# SW6106_A_A_C_MCU_LED.net
KiCad netlist of a schematic drawn in Altium Designer
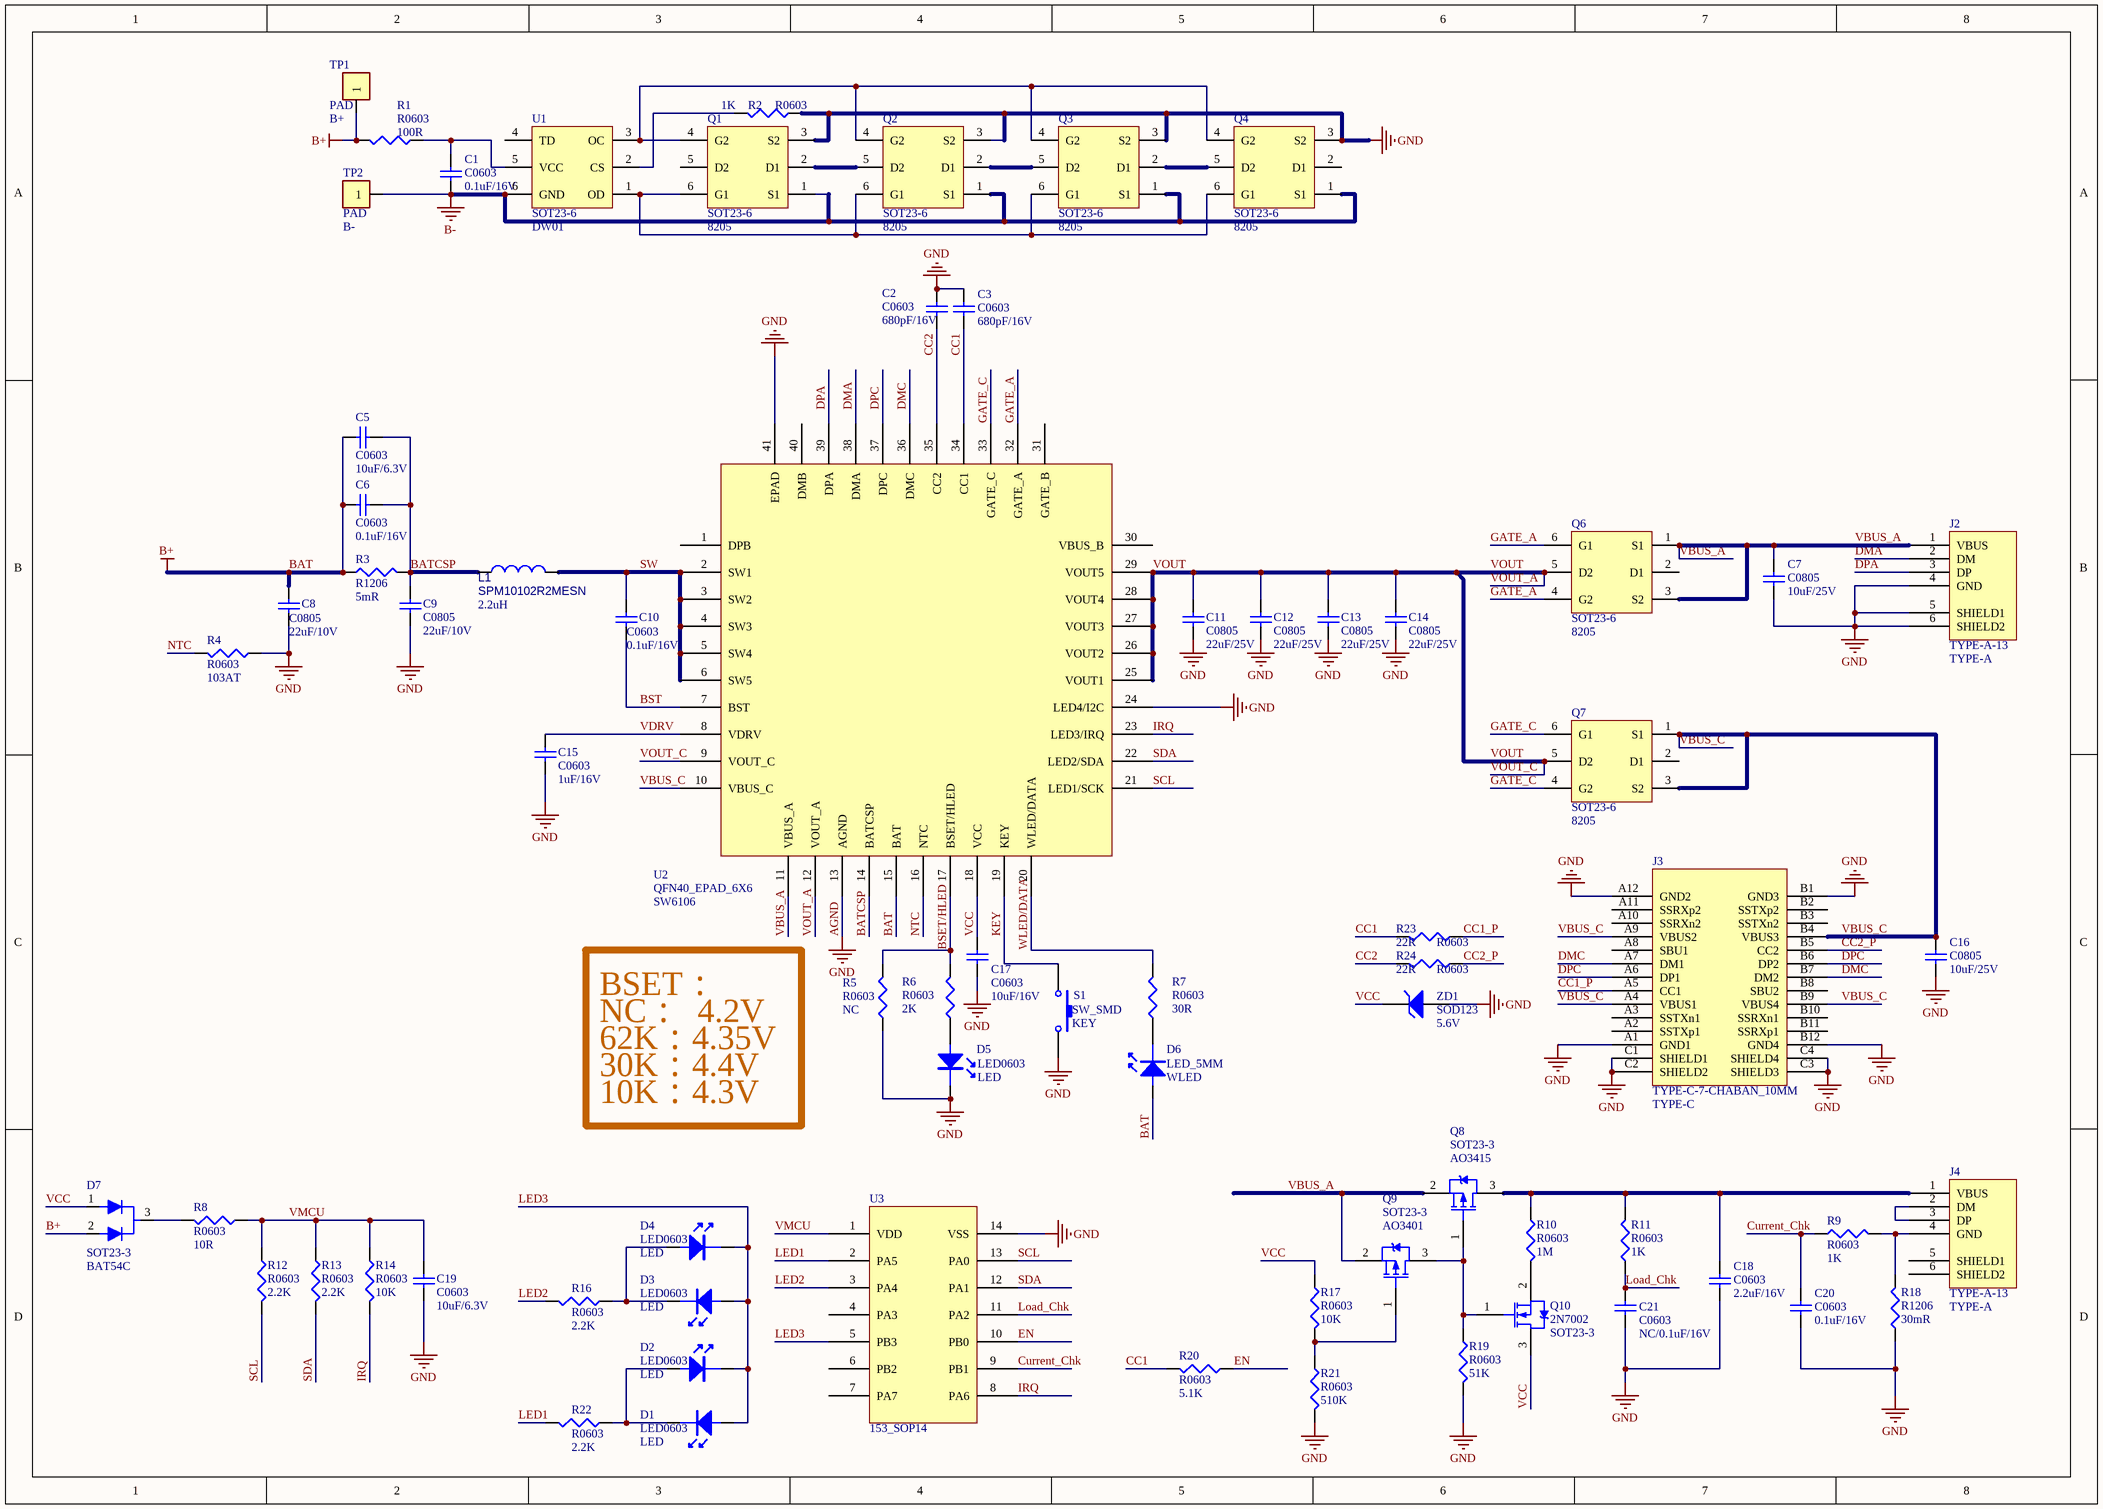
[diagram p0: SW6106+A+A+C+MCU+LED.SchDoc]

(export (version "E")
  (design (tool "Eeschema 10.0.6"))
  (components
    (comp (ref "C1")
      (value "C0603")
      (footprint "C0603")
      (description "Capacitor")
      (fields (field (name "ALTIUM_VALUE") "0.1uF/16V") (field (name "PUBLISHER") "Altium Limited"))
      (libsource (lib "*") (part "Cap"))
    )
    (comp (ref "C2")
      (value "C0603")
      (footprint "C0603")
      (description "Capacitor")
      (fields (field (name "ALTIUM_VALUE") "680pF/16V") (field (name "PUBLISHER") "Altium Limited"))
      (libsource (lib "*") (part "CAP0603"))
    )
    (comp (ref "C3")
      (value "C0603")
      (footprint "C0603")
      (description "Capacitor")
      (fields (field (name "ALTIUM_VALUE") "680pF/16V") (field (name "PUBLISHER") "Altium Limited"))
      (libsource (lib "*") (part "CAP0603"))
    )
    (comp (ref "C5")
      (value "C0603")
      (footprint "C0603")
      (description "Capacitor")
      (fields (field (name "ALTIUM_VALUE") "10uF/6.3V") (field (name "PUBLISHER") "Altium Limited"))
      (libsource (lib "*") (part "CAP0603"))
    )
    (comp (ref "C6")
      (value "C0603")
      (footprint "C0603")
      (description "Capacitor")
      (fields (field (name "ALTIUM_VALUE") "0.1uF/16V") (field (name "PUBLISHER") "Altium Limited"))
      (libsource (lib "*") (part "CAP0603"))
    )
    (comp (ref "C7")
      (value "C0805")
      (footprint "C0805")
      (description "Capacitor")
      (fields (field (name "ALTIUM_VALUE") "10uF/25V") (field (name "PUBLISHER") "Altium Limited"))
      (libsource (lib "*") (part "CAP0603"))
    )
    (comp (ref "C8")
      (value "C0805")
      (footprint "C0805")
      (description "Capacitor")
      (fields (field (name "ALTIUM_VALUE") "22uF/10V") (field (name "PUBLISHER") "Altium Limited"))
      (libsource (lib "*") (part "CAP0805"))
    )
    (comp (ref "C9")
      (value "C0805")
      (footprint "C0805")
      (description "Capacitor")
      (fields (field (name "ALTIUM_VALUE") "22uF/10V") (field (name "PUBLISHER") "Altium Limited"))
      (libsource (lib "*") (part "CAP0805"))
    )
    (comp (ref "C10")
      (value "C0603")
      (footprint "C0603")
      (description "Capacitor")
      (fields (field (name "ALTIUM_VALUE") "0.1uF/16V") (field (name "PUBLISHER") "Altium Limited"))
      (libsource (lib "*") (part "CAP0603"))
    )
    (comp (ref "C11")
      (value "C0805")
      (footprint "C0805")
      (description "Capacitor")
      (fields (field (name "ALTIUM_VALUE") "22uF/25V") (field (name "PUBLISHER") "Altium Limited"))
      (libsource (lib "*") (part "CAP0805"))
    )
    (comp (ref "C12")
      (value "C0805")
      (footprint "C0805")
      (description "Capacitor")
      (fields (field (name "ALTIUM_VALUE") "22uF/25V") (field (name "PUBLISHER") "Altium Limited"))
      (libsource (lib "*") (part "CAP0805"))
    )
    (comp (ref "C13")
      (value "C0805")
      (footprint "C0805")
      (description "Capacitor")
      (fields (field (name "ALTIUM_VALUE") "22uF/25V") (field (name "PUBLISHER") "Altium Limited"))
      (libsource (lib "*") (part "CAP0805"))
    )
    (comp (ref "C14")
      (value "C0805")
      (footprint "C0805")
      (description "Capacitor")
      (fields (field (name "ALTIUM_VALUE") "22uF/25V") (field (name "PUBLISHER") "Altium Limited"))
      (libsource (lib "*") (part "CAP0805"))
    )
    (comp (ref "C15")
      (value "C0603")
      (footprint "C0603")
      (description "Capacitor")
      (fields (field (name "ALTIUM_VALUE") "1uF/16V") (field (name "PUBLISHER") "Altium Limited"))
      (libsource (lib "*") (part "CAP0603"))
    )
    (comp (ref "C16")
      (value "C0805")
      (footprint "C0805")
      (description "Capacitor")
      (fields (field (name "ALTIUM_VALUE") "10uF/25V") (field (name "PUBLISHER") "Altium Limited"))
      (libsource (lib "*") (part "CAP0603"))
    )
    (comp (ref "C17")
      (value "C0603")
      (footprint "C0603")
      (description "Capacitor")
      (fields (field (name "ALTIUM_VALUE") "10uF/16V") (field (name "PUBLISHER") "Altium Limited"))
      (libsource (lib "*") (part "CAP0603"))
    )
    (comp (ref "C18")
      (value "C0603")
      (footprint "C0603")
      (description "Capacitor")
      (fields (field (name "ALTIUM_VALUE") "2.2uF/16V") (field (name "PUBLISHER") "Altium Limited"))
      (libsource (lib "*") (part "CAP0603"))
    )
    (comp (ref "C19")
      (value "C0603")
      (footprint "C0603")
      (description "Capacitor")
      (fields (field (name "ALTIUM_VALUE") "10uF/6.3V") (field (name "PUBLISHER") "Altium Limited"))
      (libsource (lib "*") (part "CAP0603"))
    )
    (comp (ref "C20")
      (value "C0603")
      (footprint "C0603")
      (description "Capacitor")
      (fields (field (name "ALTIUM_VALUE") "0.1uF/16V") (field (name "PUBLISHER") "Altium Limited"))
      (libsource (lib "*") (part "CAP0603"))
    )
    (comp (ref "C21")
      (value "C0603")
      (footprint "C0603")
      (description "Capacitor")
      (fields (field (name "ALTIUM_VALUE") "NC/0.1uF/16V") (field (name "PUBLISHER") "Altium Limited"))
      (libsource (lib "*") (part "CAP0603"))
    )
    (comp (ref "D1") (value "LED") (footprint "LED0603") (libsource (lib "*") (part "LED")))
    (comp (ref "D2") (value "LED") (footprint "LED0603") (libsource (lib "*") (part "LED")))
    (comp (ref "D3") (value "LED") (footprint "LED0603") (libsource (lib "*") (part "LED")))
    (comp (ref "D4") (value "LED") (footprint "LED0603") (libsource (lib "*") (part "LED")))
    (comp (ref "D5") (value "LED") (footprint "LED0603") (libsource (lib "*") (part "LED")))
    (comp (ref "D6")
      (value "WLED")
      (footprint "LED_5MM")
      (fields (field (name "FOOTPRINF") "LED_5MM") (field (name "Comment") "LED_5MM"))
      (libsource (lib "*") (part "LED"))
    )
    (comp (ref "D7") (value "BAT54C") (footprint "SOT23-3") (libsource (lib "Schlib1-2012") (part "D3")))
    (comp (ref "J2")
      (value "TYPE-A")
      (footprint "TYPE-A-13")
      (fields (field (name "FOOTPRINF") "TYPE-A-13") (field (name "Comment") "TYPE-A-1"))
      (libsource (lib "*") (part "TYPE-A-1"))
    )
    (comp (ref "J3")
      (value "TYPE-C")
      (footprint "TYPE-C-7-CHABAN_10MM")
      (libsource (lib "*") (part "TYPE-C"))
    )
    (comp (ref "J4")
      (value "TYPE-A")
      (footprint "PIE10-USB")
      (fields (field (name "FOOTPRINF") "TYPE-A-13") (field (name "Comment") "TYPE-A-1"))
      (libsource (lib "*") (part "TYPE-A-1"))
    )
    (comp (ref "L1")
      (value "SPM10102R2MESN")
      (footprint "INDUCTOR_SPM1010")
      (fields (field (name "ALTIUM_VALUE") "2.2uH"))
      (libsource (lib "*") (part "INDUCTOR"))
    )
    (comp (ref "Q1")
      (value "8205")
      (footprint "SOT23-6")
      (fields (field (name "FOOTPRINF") "SOT23-6"))
      (libsource (lib "*") (part "8205B"))
    )
    (comp (ref "Q2")
      (value "8205")
      (footprint "SOT23-6")
      (fields (field (name "FOOTPRINF") "SOT23-6"))
      (libsource (lib "*") (part "8205B"))
    )
    (comp (ref "Q3")
      (value "8205")
      (footprint "SOT23-6")
      (fields (field (name "FOOTPRINF") "SOT23-6"))
      (libsource (lib "*") (part "8205B"))
    )
    (comp (ref "Q4")
      (value "8205")
      (footprint "SOT23-6")
      (fields (field (name "FOOTPRINF") "SOT23-6"))
      (libsource (lib "*") (part "8205B"))
    )
    (comp (ref "Q6")
      (value "8205")
      (footprint "SOT23-6")
      (fields (field (name "FOOTPRINF") "SOT23-6"))
      (libsource (lib "") (part "8205B_1"))
    )
    (comp (ref "Q7")
      (value "8205")
      (footprint "SOT23-6")
      (fields (field (name "FOOTPRINF") "SOT23-6"))
      (libsource (lib "") (part "8205B_1"))
    )
    (comp (ref "Q8")
      (value "AO3415")
      (footprint "SOT23-3")
      (description "P-Channel Power MOSFET")
      (fields (field (name "Comment") "PMOS-2") (field (name "PUBLISHER") "Altium Limited"))
      (libsource (lib "Miscellaneous Devices") (part "PMOS-2"))
    )
    (comp (ref "Q9")
      (value "AO3401")
      (footprint "SOT23-3")
      (description "P-Channel Power MOSFET")
      (fields (field (name "Comment") "PMOS-2") (field (name "PUBLISHER") "Altium Limited"))
      (libsource (lib "Miscellaneous Devices") (part "PMOS-2"))
    )
    (comp (ref "Q10")
      (value "2N7002")
      (footprint "SOT23-3")
      (description "N-Channel Power MOSFET")
      (fields (field (name "Comment") "NMOS-2") (field (name "PUBLISHER") "Altium Limited"))
      (libsource (lib "Miscellaneous Devices") (part "NMOS-2"))
    )
    (comp (ref "R1")
      (value "R0603")
      (footprint "R0603")
      (description "Resistor")
      (fields (field (name "ALTIUM_VALUE") "100R") (field (name "PUBLISHER") "Altium Limited"))
      (libsource (lib "*") (part "Res3"))
    )
    (comp (ref "R2")
      (value "R0603")
      (footprint "R0603")
      (description "Resistor")
      (fields (field (name "ALTIUM_VALUE") "1K") (field (name "PUBLISHER") "Altium Limited"))
      (libsource (lib "*") (part "Res3"))
    )
    (comp (ref "R3")
      (value "R1206")
      (footprint "R1206")
      (description "Resistor")
      (fields (field (name "ALTIUM_VALUE") "5mR") (field (name "PUBLISHER") "Altium Limited"))
      (libsource (lib "*") (part "RES"))
    )
    (comp (ref "R4")
      (value "R0603")
      (footprint "R0603")
      (description "Resistor")
      (fields (field (name "ALTIUM_VALUE") "103AT") (field (name "PUBLISHER") "Altium Limited"))
      (libsource (lib "*") (part "RES"))
    )
    (comp (ref "R5")
      (value "R0603")
      (footprint "R0603")
      (description "Resistor")
      (fields (field (name "ALTIUM_VALUE") "NC") (field (name "PUBLISHER") "Altium Limited"))
      (libsource (lib "*") (part "RES"))
    )
    (comp (ref "R6")
      (value "R0603")
      (footprint "R0603")
      (description "Resistor")
      (fields (field (name "ALTIUM_VALUE") "2K") (field (name "PUBLISHER") "Altium Limited"))
      (libsource (lib "*") (part "RES"))
    )
    (comp (ref "R7")
      (value "R0603")
      (footprint "R0603")
      (description "Resistor")
      (fields (field (name "ALTIUM_VALUE") "30R") (field (name "PUBLISHER") "Altium Limited"))
      (libsource (lib "*") (part "RES"))
    )
    (comp (ref "R8")
      (value "R0603")
      (footprint "R0603")
      (description "Resistor")
      (fields (field (name "ALTIUM_VALUE") "10R") (field (name "PUBLISHER") "Altium Limited"))
      (libsource (lib "*") (part "RES"))
    )
    (comp (ref "R9")
      (value "R0603")
      (footprint "R0603")
      (description "Resistor")
      (fields (field (name "ALTIUM_VALUE") "1K") (field (name "PUBLISHER") "Altium Limited"))
      (libsource (lib "*") (part "RES"))
    )
    (comp (ref "R10")
      (value "R0603")
      (footprint "R0603")
      (description "Resistor")
      (fields (field (name "ALTIUM_VALUE") "1M") (field (name "PUBLISHER") "Altium Limited"))
      (libsource (lib "*") (part "RES"))
    )
    (comp (ref "R11")
      (value "R0603")
      (footprint "R0603")
      (description "Resistor")
      (fields (field (name "ALTIUM_VALUE") "1K") (field (name "PUBLISHER") "Altium Limited"))
      (libsource (lib "*") (part "RES"))
    )
    (comp (ref "R12")
      (value "R0603")
      (footprint "R0603")
      (description "Resistor")
      (fields (field (name "ALTIUM_VALUE") "2.2K") (field (name "PUBLISHER") "Altium Limited"))
      (libsource (lib "*") (part "RES"))
    )
    (comp (ref "R13")
      (value "R0603")
      (footprint "R0603")
      (description "Resistor")
      (fields (field (name "ALTIUM_VALUE") "2.2K") (field (name "PUBLISHER") "Altium Limited"))
      (libsource (lib "*") (part "RES"))
    )
    (comp (ref "R14")
      (value "R0603")
      (footprint "R0603")
      (description "Resistor")
      (fields (field (name "ALTIUM_VALUE") "10K") (field (name "PUBLISHER") "Altium Limited"))
      (libsource (lib "*") (part "RES"))
    )
    (comp (ref "R16")
      (value "R0603")
      (footprint "R0603")
      (description "Resistor")
      (fields (field (name "ALTIUM_VALUE") "2.2K") (field (name "PUBLISHER") "Altium Limited"))
      (libsource (lib "*") (part "RES"))
    )
    (comp (ref "R17")
      (value "R0603")
      (footprint "R0603")
      (description "Resistor")
      (fields (field (name "ALTIUM_VALUE") "10K") (field (name "PUBLISHER") "Altium Limited"))
      (libsource (lib "*") (part "RES"))
    )
    (comp (ref "R18")
      (value "R1206")
      (footprint "C-1206A")
      (description "Resistor")
      (fields (field (name "ALTIUM_VALUE") "30mR") (field (name "PUBLISHER") "Altium Limited"))
      (libsource (lib "*") (part "RES"))
    )
    (comp (ref "R19")
      (value "R0603")
      (footprint "R0603")
      (description "Resistor")
      (fields (field (name "ALTIUM_VALUE") "51K") (field (name "PUBLISHER") "Altium Limited"))
      (libsource (lib "*") (part "RES"))
    )
    (comp (ref "R20")
      (value "R0603")
      (footprint "R0603")
      (description "Resistor")
      (fields (field (name "ALTIUM_VALUE") "5.1K") (field (name "PUBLISHER") "Altium Limited"))
      (libsource (lib "*") (part "RES"))
    )
    (comp (ref "R21")
      (value "R0603")
      (footprint "R0603")
      (description "Resistor")
      (fields (field (name "ALTIUM_VALUE") "510K") (field (name "PUBLISHER") "Altium Limited"))
      (libsource (lib "*") (part "RES"))
    )
    (comp (ref "R22")
      (value "R0603")
      (footprint "R0603")
      (description "Resistor")
      (fields (field (name "ALTIUM_VALUE") "2.2K") (field (name "PUBLISHER") "Altium Limited"))
      (libsource (lib "*") (part "RES"))
    )
    (comp (ref "R23")
      (value "R0603")
      (footprint "R0603")
      (description "Resistor")
      (fields (field (name "ALTIUM_VALUE") "22R") (field (name "PUBLISHER") "Altium Limited"))
      (libsource (lib "*") (part "RES"))
    )
    (comp (ref "R24")
      (value "R0603")
      (footprint "R0603")
      (description "Resistor")
      (fields (field (name "ALTIUM_VALUE") "22R") (field (name "PUBLISHER") "Altium Limited"))
      (libsource (lib "*") (part "RES"))
    )
    (comp (ref "S1")
      (value "KEY")
      (footprint "SW_SMD")
      (fields (field (name "FOOTPRINF") "SW_SMD"))
      (libsource (lib "*") (part "SW K"))
    )
    (comp (ref "TP1") (value "B+") (footprint "PAD") (libsource (lib "*") (part "Test Point")))
    (comp (ref "TP2") (value "B-") (footprint "PAD") (libsource (lib "") (part "Test Point_1")))
    (comp (ref "U1")
      (value "DW01")
      (footprint "SOT23-6")
      (fields (field (name "FOOTPRINF") "SOT23-6"))
      (libsource (lib "*") (part "DW01"))
    )
    (comp (ref "U2")
      (value "SW6106")
      (footprint "QFN40_EPAD_6X6")
      (libsource (lib "TEST") (part "SW6106_AFC"))
    )
    (comp (ref "U3") (value "153_SOP14") (libsource (lib "TEST") (part "153_SOP14")))
    (comp (ref "ZD1")
      (value "SOD123")
      (footprint "SOD-123")
      (description "Zener Diode")
      (fields (field (name "ALTIUM_UNNAMED_1") "5.6V"))
      (libsource (lib "Miscellaneous Devices") (part "D Zener"))
    )
  )
  (nets
    (net (code "1") (name "/BATCSP") (class "Default")
      (node (ref "C5") (pin "2") (pinfunction "2_2") (pintype "passive"))
      (node (ref "C6") (pin "2") (pinfunction "2_2") (pintype "passive"))
      (node (ref "C9") (pin "2") (pinfunction "2_2") (pintype "passive"))
      (node (ref "L1") (pin "1") (pinfunction "1_1") (pintype "passive"))
      (node (ref "R3") (pin "2") (pinfunction "2_2") (pintype "passive"))
      (node (ref "U2") (pin "14") (pinfunction "BATCSP_14") (pintype "passive"))
    )
    (net (code "2") (name "/BSET{slash}HLED") (class "Default")
      (node (ref "R5") (pin "2") (pinfunction "2_2") (pintype "passive"))
      (node (ref "R6") (pin "2") (pinfunction "2_2") (pintype "passive"))
      (node (ref "U2") (pin "17") (pinfunction "BSET/HLED_17") (pintype "passive"))
    )
    (net (code "3") (name "/BST") (class "Default")
      (node (ref "C10") (pin "1") (pinfunction "1_1") (pintype "passive"))
      (node (ref "U2") (pin "7") (pinfunction "BST_7") (pintype "passive"))
    )
    (net (code "4") (name "/CC1") (class "Default")
      (node (ref "C3") (pin "1") (pinfunction "1_1") (pintype "passive"))
      (node (ref "R20") (pin "2") (pinfunction "2_2") (pintype "passive"))
      (node (ref "R23") (pin "2") (pinfunction "2_2") (pintype "passive"))
      (node (ref "U2") (pin "34") (pinfunction "CC1_34") (pintype "passive"))
    )
    (net (code "5") (name "/CC1_P") (class "Default")
      (node (ref "J3") (pin "A5") (pinfunction "CC1_A5") (pintype "passive"))
      (node (ref "R23") (pin "1") (pinfunction "1_1") (pintype "passive"))
    )
    (net (code "6") (name "/CC2") (class "Default")
      (node (ref "C2") (pin "1") (pinfunction "1_1") (pintype "passive"))
      (node (ref "R24") (pin "2") (pinfunction "2_2") (pintype "passive"))
      (node (ref "U2") (pin "35") (pinfunction "CC2_35") (pintype "passive"))
    )
    (net (code "7") (name "/CC2_P") (class "Default")
      (node (ref "J3") (pin "B5") (pinfunction "CC2_B5") (pintype "passive"))
      (node (ref "R24") (pin "1") (pinfunction "1_1") (pintype "passive"))
    )
    (net (code "8") (name "/Current_Chk") (class "Default")
      (node (ref "C20") (pin "2") (pinfunction "2_2") (pintype "passive"))
      (node (ref "R9") (pin "1") (pinfunction "1_1") (pintype "passive"))
      (node (ref "U3") (pin "9") (pinfunction "PB1_9") (pintype "passive"))
    )
    (net (code "9") (name "/DMA") (class "Default")
      (node (ref "J2") (pin "2") (pinfunction "DM_2") (pintype "passive"))
      (node (ref "U2") (pin "38") (pinfunction "DMA_38") (pintype "passive"))
    )
    (net (code "10") (name "/DMC") (class "Default")
      (node (ref "J3") (pin "A7") (pinfunction "DM1_A7") (pintype "passive"))
      (node (ref "J3") (pin "B7") (pinfunction "DM2_B7") (pintype "passive"))
      (node (ref "U2") (pin "36") (pinfunction "DMC_36") (pintype "passive"))
    )
    (net (code "11") (name "/DPA") (class "Default")
      (node (ref "J2") (pin "3") (pinfunction "DP_3") (pintype "passive"))
      (node (ref "U2") (pin "39") (pinfunction "DPA_39") (pintype "passive"))
    )
    (net (code "12") (name "/DPC") (class "Default")
      (node (ref "J3") (pin "A6") (pinfunction "DP1_A6") (pintype "passive"))
      (node (ref "J3") (pin "B6") (pinfunction "DP2_B6") (pintype "passive"))
      (node (ref "U2") (pin "37") (pinfunction "DPC_37") (pintype "passive"))
    )
    (net (code "13") (name "/EN") (class "Default")
      (node (ref "R20") (pin "1") (pinfunction "1_1") (pintype "passive"))
      (node (ref "U3") (pin "10") (pinfunction "PB0_10") (pintype "passive"))
    )
    (net (code "14") (name "/GATE_A") (class "Default")
      (node (ref "Q6") (pin "4") (pinfunction "G2_4") (pintype "passive"))
      (node (ref "Q6") (pin "6") (pinfunction "G1_6") (pintype "passive"))
      (node (ref "U2") (pin "32") (pinfunction "GATE_A_32") (pintype "passive"))
    )
    (net (code "15") (name "/GATE_C") (class "Default")
      (node (ref "Q7") (pin "4") (pinfunction "G2_4") (pintype "passive"))
      (node (ref "Q7") (pin "6") (pinfunction "G1_6") (pintype "passive"))
      (node (ref "U2") (pin "33") (pinfunction "GATE_C_33") (pintype "passive"))
    )
    (net (code "16") (name "/IRQ") (class "Default")
      (node (ref "R14") (pin "2") (pinfunction "2_2") (pintype "passive"))
      (node (ref "U2") (pin "23") (pinfunction "LED3/IRQ_23") (pintype "passive"))
      (node (ref "U3") (pin "8") (pinfunction "PA6_8") (pintype "passive"))
    )
    (net (code "17") (name "/KEY") (class "Default")
      (node (ref "S1") (pin "1") (pinfunction "1_1") (pintype "passive"))
      (node (ref "U2") (pin "19") (pinfunction "KEY_19") (pintype "passive"))
    )
    (net (code "18") (name "/LED1") (class "Default")
      (node (ref "R22") (pin "2") (pinfunction "2_2") (pintype "passive"))
      (node (ref "U3") (pin "2") (pinfunction "PA5_2") (pintype "passive"))
    )
    (net (code "19") (name "/LED2") (class "Default")
      (node (ref "R16") (pin "2") (pinfunction "2_2") (pintype "passive"))
      (node (ref "U3") (pin "3") (pinfunction "PA4_3") (pintype "passive"))
    )
    (net (code "20") (name "/LED3") (class "Default")
      (node (ref "D1") (pin "1") (pinfunction "A_1") (pintype "passive"))
      (node (ref "D2") (pin "2") (pinfunction "K_2") (pintype "passive"))
      (node (ref "D3") (pin "1") (pinfunction "A_1") (pintype "passive"))
      (node (ref "D4") (pin "2") (pinfunction "K_2") (pintype "passive"))
      (node (ref "U3") (pin "5") (pinfunction "PB3_5") (pintype "passive"))
    )
    (net (code "21") (name "/Load_Chk") (class "Default")
      (node (ref "C21") (pin "2") (pinfunction "2_2") (pintype "passive"))
      (node (ref "R11") (pin "1") (pinfunction "1_1") (pintype "passive"))
      (node (ref "U3") (pin "11") (pinfunction "PA2_11") (pintype "passive"))
    )
    (net (code "22") (name "/NTC") (class "Default")
      (node (ref "R4") (pin "2") (pinfunction "2_2") (pintype "passive"))
      (node (ref "U2") (pin "16") (pinfunction "NTC_16") (pintype "passive"))
    )
    (net (code "23") (name "/SCL") (class "Default")
      (node (ref "R12") (pin "2") (pinfunction "2_2") (pintype "passive"))
      (node (ref "U2") (pin "21") (pinfunction "LED1/SCK_21") (pintype "passive"))
      (node (ref "U3") (pin "13") (pinfunction "PA0_13") (pintype "passive"))
    )
    (net (code "24") (name "/SDA") (class "Default")
      (node (ref "R13") (pin "2") (pinfunction "2_2") (pintype "passive"))
      (node (ref "U2") (pin "22") (pinfunction "LED2/SDA_22") (pintype "passive"))
      (node (ref "U3") (pin "12") (pinfunction "PA1_12") (pintype "passive"))
    )
    (net (code "25") (name "/SW") (class "Default")
      (node (ref "C10") (pin "2") (pinfunction "2_2") (pintype "passive"))
      (node (ref "L1") (pin "2") (pinfunction "2_2") (pintype "passive"))
      (node (ref "U2") (pin "2") (pinfunction "SW1_2") (pintype "passive"))
      (node (ref "U2") (pin "3") (pinfunction "SW2_3") (pintype "passive"))
      (node (ref "U2") (pin "4") (pinfunction "SW3_4") (pintype "passive"))
      (node (ref "U2") (pin "5") (pinfunction "SW4_5") (pintype "passive"))
      (node (ref "U2") (pin "6") (pinfunction "SW5_6") (pintype "passive"))
    )
    (net (code "26") (name "/VBUS_A") (class "Default")
      (node (ref "C7") (pin "2") (pinfunction "2_2") (pintype "passive"))
      (node (ref "J2") (pin "1") (pinfunction "VBUS_1") (pintype "passive"))
      (node (ref "Q6") (pin "1") (pinfunction "S1_1") (pintype "passive"))
      (node (ref "Q6") (pin "3") (pinfunction "S2_3") (pintype "passive"))
      (node (ref "Q8") (pin "2") (pinfunction "S_2") (pintype "passive"))
      (node (ref "Q9") (pin "2") (pinfunction "S_2") (pintype "passive"))
      (node (ref "U2") (pin "11") (pinfunction "VBUS_A_11") (pintype "passive"))
    )
    (net (code "27") (name "/VBUS_C") (class "Default")
      (node (ref "C16") (pin "2") (pinfunction "2_2") (pintype "passive"))
      (node (ref "J3") (pin "A4") (pinfunction "VBUS1_A4") (pintype "passive"))
      (node (ref "J3") (pin "A9") (pinfunction "VBUS2_A9") (pintype "passive"))
      (node (ref "J3") (pin "B4") (pinfunction "VBUS3_B4") (pintype "passive"))
      (node (ref "J3") (pin "B9") (pinfunction "VBUS4_B9") (pintype "passive"))
      (node (ref "Q7") (pin "1") (pinfunction "S1_1") (pintype "passive"))
      (node (ref "Q7") (pin "3") (pinfunction "S2_3") (pintype "passive"))
      (node (ref "U2") (pin "10") (pinfunction "VBUS_C_10") (pintype "passive"))
    )
    (net (code "28") (name "/VCC") (class "Default")
      (node (ref "C17") (pin "2") (pinfunction "2_2") (pintype "passive"))
      (node (ref "D7") (pin "1") (pintype "passive"))
      (node (ref "Q10") (pin "3") (pinfunction "D_3") (pintype "passive"))
      (node (ref "R17") (pin "1") (pinfunction "1_1") (pintype "passive"))
      (node (ref "U2") (pin "18") (pinfunction "VCC_18") (pintype "passive"))
      (node (ref "ZD1") (pin "2") (pinfunction "K_2") (pintype "passive"))
    )
    (net (code "29") (name "/VDRV") (class "Default")
      (node (ref "C15") (pin "2") (pinfunction "2_2") (pintype "passive"))
      (node (ref "U2") (pin "8") (pinfunction "VDRV_8") (pintype "passive"))
    )
    (net (code "30") (name "/VMCU") (class "Default")
      (node (ref "C19") (pin "1") (pinfunction "1_1") (pintype "passive"))
      (node (ref "R12") (pin "1") (pinfunction "1_1") (pintype "passive"))
      (node (ref "R13") (pin "1") (pinfunction "1_1") (pintype "passive"))
      (node (ref "R14") (pin "1") (pinfunction "1_1") (pintype "passive"))
      (node (ref "R8") (pin "1") (pinfunction "1_1") (pintype "passive"))
      (node (ref "U3") (pin "1") (pinfunction "VDD_1") (pintype "passive"))
    )
    (net (code "31") (name "/VOUT") (class "Default")
      (node (ref "C11") (pin "2") (pinfunction "2_2") (pintype "passive"))
      (node (ref "C12") (pin "2") (pinfunction "2_2") (pintype "passive"))
      (node (ref "C13") (pin "2") (pinfunction "2_2") (pintype "passive"))
      (node (ref "C14") (pin "2") (pinfunction "2_2") (pintype "passive"))
      (node (ref "Q6") (pin "5") (pinfunction "D2_5") (pintype "passive"))
      (node (ref "Q7") (pin "5") (pinfunction "D2_5") (pintype "passive"))
      (node (ref "U2") (pin "12") (pinfunction "VOUT_A_12") (pintype "passive"))
      (node (ref "U2") (pin "25") (pinfunction "VOUT1_25") (pintype "passive"))
      (node (ref "U2") (pin "26") (pinfunction "VOUT2_26") (pintype "passive"))
      (node (ref "U2") (pin "27") (pinfunction "VOUT3_27") (pintype "passive"))
      (node (ref "U2") (pin "28") (pinfunction "VOUT4_28") (pintype "passive"))
      (node (ref "U2") (pin "29") (pinfunction "VOUT5_29") (pintype "passive"))
      (node (ref "U2") (pin "9") (pinfunction "VOUT_C_9") (pintype "passive"))
    )
    (net (code "32") (name "/WLED{slash}DATA") (class "Default")
      (node (ref "R7") (pin "2") (pinfunction "2_2") (pintype "passive"))
      (node (ref "U2") (pin "20") (pinfunction "WLED/DATA_20") (pintype "passive"))
    )
    (net (code "33") (name "B+") (class "Default")
      (node (ref "C5") (pin "1") (pinfunction "1_1") (pintype "passive"))
      (node (ref "C6") (pin "1") (pinfunction "1_1") (pintype "passive"))
      (node (ref "C8") (pin "2") (pinfunction "2_2") (pintype "passive"))
      (node (ref "D6") (pin "1") (pinfunction "A_1") (pintype "passive"))
      (node (ref "D7") (pin "2") (pintype "passive"))
      (node (ref "R1") (pin "2") (pinfunction "2_2") (pintype "passive"))
      (node (ref "R3") (pin "1") (pinfunction "1_1") (pintype "passive"))
      (node (ref "TP1") (pin "1") (pinfunction "1_1") (pintype "passive"))
      (node (ref "U2") (pin "15") (pinfunction "BAT_15") (pintype "passive"))
    )
    (net (code "34") (name "B-") (class "Default")
      (node (ref "C1") (pin "1") (pinfunction "1_1") (pintype "passive"))
      (node (ref "Q1") (pin "1") (pinfunction "S1_1") (pintype "passive"))
      (node (ref "Q2") (pin "1") (pinfunction "S1_1") (pintype "passive"))
      (node (ref "Q3") (pin "1") (pinfunction "S1_1") (pintype "passive"))
      (node (ref "Q4") (pin "1") (pinfunction "S1_1") (pintype "passive"))
      (node (ref "TP2") (pin "1") (pinfunction "1_1") (pintype "passive"))
      (node (ref "U1") (pin "6") (pinfunction "GND_6") (pintype "passive"))
    )
    (net (code "35") (name "GND") (class "Default")
      (node (ref "C11") (pin "1") (pinfunction "1_1") (pintype "passive"))
      (node (ref "C12") (pin "1") (pinfunction "1_1") (pintype "passive"))
      (node (ref "C13") (pin "1") (pinfunction "1_1") (pintype "passive"))
      (node (ref "C14") (pin "1") (pinfunction "1_1") (pintype "passive"))
      (node (ref "C15") (pin "1") (pinfunction "1_1") (pintype "passive"))
      (node (ref "C16") (pin "1") (pinfunction "1_1") (pintype "passive"))
      (node (ref "C17") (pin "1") (pinfunction "1_1") (pintype "passive"))
      (node (ref "C18") (pin "1") (pinfunction "1_1") (pintype "passive"))
      (node (ref "C19") (pin "2") (pinfunction "2_2") (pintype "passive"))
      (node (ref "C2") (pin "2") (pinfunction "2_2") (pintype "passive"))
      (node (ref "C20") (pin "1") (pinfunction "1_1") (pintype "passive"))
      (node (ref "C21") (pin "1") (pinfunction "1_1") (pintype "passive"))
      (node (ref "C3") (pin "2") (pinfunction "2_2") (pintype "passive"))
      (node (ref "C7") (pin "1") (pinfunction "1_1") (pintype "passive"))
      (node (ref "C8") (pin "1") (pinfunction "1_1") (pintype "passive"))
      (node (ref "C9") (pin "1") (pinfunction "1_1") (pintype "passive"))
      (node (ref "D5") (pin "2") (pinfunction "K_2") (pintype "passive"))
      (node (ref "J2") (pin "4") (pinfunction "GND_4") (pintype "passive"))
      (node (ref "J2") (pin "5") (pinfunction "SHIELD1_5") (pintype "passive"))
      (node (ref "J2") (pin "6") (pinfunction "SHIELD2_6") (pintype "passive"))
      (node (ref "J3") (pin "A1") (pinfunction "GND1_A1") (pintype "passive"))
      (node (ref "J3") (pin "A12") (pinfunction "GND2_A12") (pintype "passive"))
      (node (ref "J3") (pin "B1") (pinfunction "GND3_B1") (pintype "passive"))
      (node (ref "J3") (pin "B12") (pinfunction "GND4_B12") (pintype "passive"))
      (node (ref "J3") (pin "C1") (pinfunction "SHIELD1_C1") (pintype "passive"))
      (node (ref "J3") (pin "C2") (pinfunction "SHIELD2_C2") (pintype "passive"))
      (node (ref "J3") (pin "C3") (pinfunction "SHIELD3_C3") (pintype "passive"))
      (node (ref "J3") (pin "C4") (pinfunction "SHIELD4_C4") (pintype "passive"))
      (node (ref "Q1") (pin "3") (pinfunction "S2_3") (pintype "passive"))
      (node (ref "Q2") (pin "3") (pinfunction "S2_3") (pintype "passive"))
      (node (ref "Q3") (pin "3") (pinfunction "S2_3") (pintype "passive"))
      (node (ref "Q4") (pin "3") (pinfunction "S2_3") (pintype "passive"))
      (node (ref "R18") (pin "1") (pinfunction "1_1") (pintype "passive"))
      (node (ref "R19") (pin "2") (pinfunction "2_2") (pintype "passive"))
      (node (ref "R2") (pin "1") (pinfunction "1_1") (pintype "passive"))
      (node (ref "R21") (pin "2") (pinfunction "2_2") (pintype "passive"))
      (node (ref "R4") (pin "1") (pinfunction "1_1") (pintype "passive"))
      (node (ref "R5") (pin "1") (pinfunction "1_1") (pintype "passive"))
      (node (ref "S1") (pin "2") (pinfunction "2_2") (pintype "passive"))
      (node (ref "U2") (pin "13") (pinfunction "AGND_13") (pintype "passive"))
      (node (ref "U2") (pin "24") (pinfunction "LED4/I2C_24") (pintype "passive"))
      (node (ref "U2") (pin "41") (pinfunction "EPAD_41") (pintype "passive"))
      (node (ref "U3") (pin "14") (pinfunction "VSS_14") (pintype "passive"))
      (node (ref "ZD1") (pin "1") (pinfunction "A_1") (pintype "passive"))
    )
    (net (code "36") (name "Net-(D1-K)") (class "Default")
      (node (ref "D1") (pin "2") (pinfunction "K_2") (pintype "passive"))
      (node (ref "D2") (pin "1") (pinfunction "A_1") (pintype "passive"))
      (node (ref "R22") (pin "1") (pinfunction "1_1") (pintype "passive"))
    )
    (net (code "37") (name "Net-(D3-K)") (class "Default")
      (node (ref "D3") (pin "2") (pinfunction "K_2") (pintype "passive"))
      (node (ref "D4") (pin "1") (pinfunction "A_1") (pintype "passive"))
      (node (ref "R16") (pin "1") (pinfunction "1_1") (pintype "passive"))
    )
    (net (code "38") (name "Net-(D5-A)") (class "Default")
      (node (ref "D5") (pin "1") (pinfunction "A_1") (pintype "passive"))
      (node (ref "R6") (pin "1") (pinfunction "1_1") (pintype "passive"))
    )
    (net (code "39") (name "Net-(D6-K)") (class "Default")
      (node (ref "D6") (pin "2") (pinfunction "K_2") (pintype "passive"))
      (node (ref "R7") (pin "1") (pinfunction "1_1") (pintype "passive"))
    )
    (net (code "40") (name "Net-(D7-Pad3)") (class "Default")
      (node (ref "D7") (pin "3") (pintype "passive"))
      (node (ref "R8") (pin "2") (pinfunction "2_2") (pintype "passive"))
    )
    (net (code "41") (name "Net-(J4-DM)") (class "Default")
      (node (ref "J4") (pin "2") (pinfunction "DM_2") (pintype "passive"))
      (node (ref "J4") (pin "3") (pinfunction "DP_3") (pintype "passive"))
    )
    (net (code "42") (name "Net-(J4-GND)") (class "Default")
      (node (ref "J4") (pin "4") (pinfunction "GND_4") (pintype "passive"))
      (node (ref "R18") (pin "2") (pinfunction "2_2") (pintype "passive"))
      (node (ref "R9") (pin "2") (pinfunction "2_2") (pintype "passive"))
    )
    (net (code "43") (name "Net-(J4-VBUS)") (class "Default")
      (node (ref "C18") (pin "2") (pinfunction "2_2") (pintype "passive"))
      (node (ref "J4") (pin "1") (pinfunction "VBUS_1") (pintype "passive"))
      (node (ref "Q8") (pin "3") (pinfunction "D_3") (pintype "passive"))
      (node (ref "R10") (pin "1") (pinfunction "1_1") (pintype "passive"))
      (node (ref "R11") (pin "2") (pinfunction "2_2") (pintype "passive"))
    )
    (net (code "44") (name "Net-(Q1-D1)") (class "Default")
      (node (ref "Q1") (pin "2") (pinfunction "D1_2") (pintype "passive"))
      (node (ref "Q2") (pin "5") (pinfunction "D2_5") (pintype "passive"))
    )
    (net (code "45") (name "Net-(Q1-G1)") (class "Default")
      (node (ref "Q1") (pin "6") (pinfunction "G1_6") (pintype "passive"))
      (node (ref "Q2") (pin "6") (pinfunction "G1_6") (pintype "passive"))
      (node (ref "Q3") (pin "6") (pinfunction "G1_6") (pintype "passive"))
      (node (ref "Q4") (pin "6") (pinfunction "G1_6") (pintype "passive"))
      (node (ref "U1") (pin "1") (pinfunction "OD_1") (pintype "passive"))
    )
    (net (code "46") (name "Net-(Q1-G2)") (class "Default")
      (node (ref "Q1") (pin "4") (pinfunction "G2_4") (pintype "passive"))
      (node (ref "Q2") (pin "4") (pinfunction "G2_4") (pintype "passive"))
      (node (ref "Q3") (pin "4") (pinfunction "G2_4") (pintype "passive"))
      (node (ref "Q4") (pin "4") (pinfunction "G2_4") (pintype "passive"))
      (node (ref "U1") (pin "3") (pinfunction "OC_3") (pintype "passive"))
    )
    (net (code "47") (name "Net-(Q2-D1)") (class "Default")
      (node (ref "Q2") (pin "2") (pinfunction "D1_2") (pintype "passive"))
      (node (ref "Q3") (pin "5") (pinfunction "D2_5") (pintype "passive"))
    )
    (net (code "48") (name "Net-(Q3-D1)") (class "Default")
      (node (ref "Q3") (pin "2") (pinfunction "D1_2") (pintype "passive"))
      (node (ref "Q4") (pin "5") (pinfunction "D2_5") (pintype "passive"))
    )
    (net (code "49") (name "Net-(Q9-G)") (class "Default")
      (node (ref "Q9") (pin "1") (pinfunction "G_1") (pintype "passive"))
      (node (ref "R17") (pin "2") (pinfunction "2_2") (pintype "passive"))
      (node (ref "R21") (pin "1") (pinfunction "1_1") (pintype "passive"))
    )
    (net (code "50") (name "Net-(Q10-G)") (class "Default")
      (node (ref "Q10") (pin "1") (pinfunction "G_1") (pintype "passive"))
      (node (ref "Q8") (pin "1") (pinfunction "G_1") (pintype "passive"))
      (node (ref "Q9") (pin "3") (pinfunction "D_3") (pintype "passive"))
      (node (ref "R19") (pin "1") (pinfunction "1_1") (pintype "passive"))
    )
    (net (code "51") (name "Net-(Q10-S)") (class "Default")
      (node (ref "Q10") (pin "2") (pinfunction "S_2") (pintype "passive"))
      (node (ref "R10") (pin "2") (pinfunction "2_2") (pintype "passive"))
    )
    (net (code "52") (name "Net-(U1-CS)") (class "Default")
      (node (ref "R2") (pin "2") (pinfunction "2_2") (pintype "passive"))
      (node (ref "U1") (pin "2") (pinfunction "CS_2") (pintype "passive"))
    )
    (net (code "53") (name "Net-(U1-VCC)") (class "Default")
      (node (ref "C1") (pin "2") (pinfunction "2_2") (pintype "passive"))
      (node (ref "R1") (pin "1") (pinfunction "1_1") (pintype "passive"))
      (node (ref "U1") (pin "5") (pinfunction "VCC_5") (pintype "passive"))
    )
    (net (code "54") (name "unconnected-(J3-SBU1-PadA8)") (class "Default")
      (node (ref "J3") (pin "A8") (pinfunction "SBU1_A8") (pintype "passive"))
    )
    (net (code "55") (name "unconnected-(J3-SBU2-PadB8)") (class "Default")
      (node (ref "J3") (pin "B8") (pinfunction "SBU2_B8") (pintype "passive"))
    )
    (net (code "56") (name "unconnected-(J3-SSRXn1-PadB10)") (class "Default")
      (node (ref "J3") (pin "B10") (pinfunction "SSRXn1_B10") (pintype "passive"))
    )
    (net (code "57") (name "unconnected-(J3-SSRXn2-PadA10)") (class "Default")
      (node (ref "J3") (pin "A10") (pinfunction "SSRXn2_A10") (pintype "passive"))
    )
    (net (code "58") (name "unconnected-(J3-SSRXp1-PadB11)") (class "Default")
      (node (ref "J3") (pin "B11") (pinfunction "SSRXp1_B11") (pintype "passive"))
    )
    (net (code "59") (name "unconnected-(J3-SSRXp2-PadA11)") (class "Default")
      (node (ref "J3") (pin "A11") (pinfunction "SSRXp2_A11") (pintype "passive"))
    )
    (net (code "60") (name "unconnected-(J3-SSTXn1-PadA3)") (class "Default")
      (node (ref "J3") (pin "A3") (pinfunction "SSTXn1_A3") (pintype "passive"))
    )
    (net (code "61") (name "unconnected-(J3-SSTXn2-PadB3)") (class "Default")
      (node (ref "J3") (pin "B3") (pinfunction "SSTXn2_B3") (pintype "passive"))
    )
    (net (code "62") (name "unconnected-(J3-SSTXp1-PadA2)") (class "Default")
      (node (ref "J3") (pin "A2") (pinfunction "SSTXp1_A2") (pintype "passive"))
    )
    (net (code "63") (name "unconnected-(J3-SSTXp2-PadB2)") (class "Default")
      (node (ref "J3") (pin "B2") (pinfunction "SSTXp2_B2") (pintype "passive"))
    )
    (net (code "64") (name "unconnected-(J4-SHIELD1-Pad5)") (class "Default")
      (node (ref "J4") (pin "5") (pinfunction "SHIELD1_5") (pintype "passive"))
    )
    (net (code "65") (name "unconnected-(J4-SHIELD2-Pad6)") (class "Default")
      (node (ref "J4") (pin "6") (pinfunction "SHIELD2_6") (pintype "passive"))
    )
    (net (code "66") (name "unconnected-(Q1-D2-Pad5)") (class "Default")
      (node (ref "Q1") (pin "5") (pinfunction "D2_5") (pintype "passive"))
    )
    (net (code "67") (name "unconnected-(Q4-D1-Pad2)") (class "Default")
      (node (ref "Q4") (pin "2") (pinfunction "D1_2") (pintype "passive"))
    )
    (net (code "68") (name "unconnected-(Q6-D1-Pad2)") (class "Default")
      (node (ref "Q6") (pin "2") (pinfunction "D1_2") (pintype "passive"))
    )
    (net (code "69") (name "unconnected-(Q7-D1-Pad2)") (class "Default")
      (node (ref "Q7") (pin "2") (pinfunction "D1_2") (pintype "passive"))
    )
    (net (code "70") (name "unconnected-(U1-TD-Pad4)") (class "Default")
      (node (ref "U1") (pin "4") (pinfunction "TD_4") (pintype "passive"))
    )
    (net (code "71") (name "unconnected-(U2-DMB-Pad40)") (class "Default")
      (node (ref "U2") (pin "40") (pinfunction "DMB_40") (pintype "passive"))
    )
    (net (code "72") (name "unconnected-(U2-DPB-Pad1)") (class "Default")
      (node (ref "U2") (pin "1") (pinfunction "DPB_1") (pintype "passive"))
    )
    (net (code "73") (name "unconnected-(U2-GATE_B-Pad31)") (class "Default")
      (node (ref "U2") (pin "31") (pinfunction "GATE_B_31") (pintype "passive"))
    )
    (net (code "74") (name "unconnected-(U2-VBUS_B-Pad30)") (class "Default")
      (node (ref "U2") (pin "30") (pinfunction "VBUS_B_30") (pintype "passive"))
    )
    (net (code "75") (name "unconnected-(U3-PA3-Pad4)") (class "Default")
      (node (ref "U3") (pin "4") (pinfunction "PA3_4") (pintype "passive"))
    )
    (net (code "76") (name "unconnected-(U3-PA7-Pad7)") (class "Default")
      (node (ref "U3") (pin "7") (pinfunction "PA7_7") (pintype "passive"))
    )
    (net (code "77") (name "unconnected-(U3-PB2-Pad6)") (class "Default")
      (node (ref "U3") (pin "6") (pinfunction "PB2_6") (pintype "passive"))
    )
  )
)
